# TA_kontroller.net
KiCad netlist of a schematic drawn in EAGLE
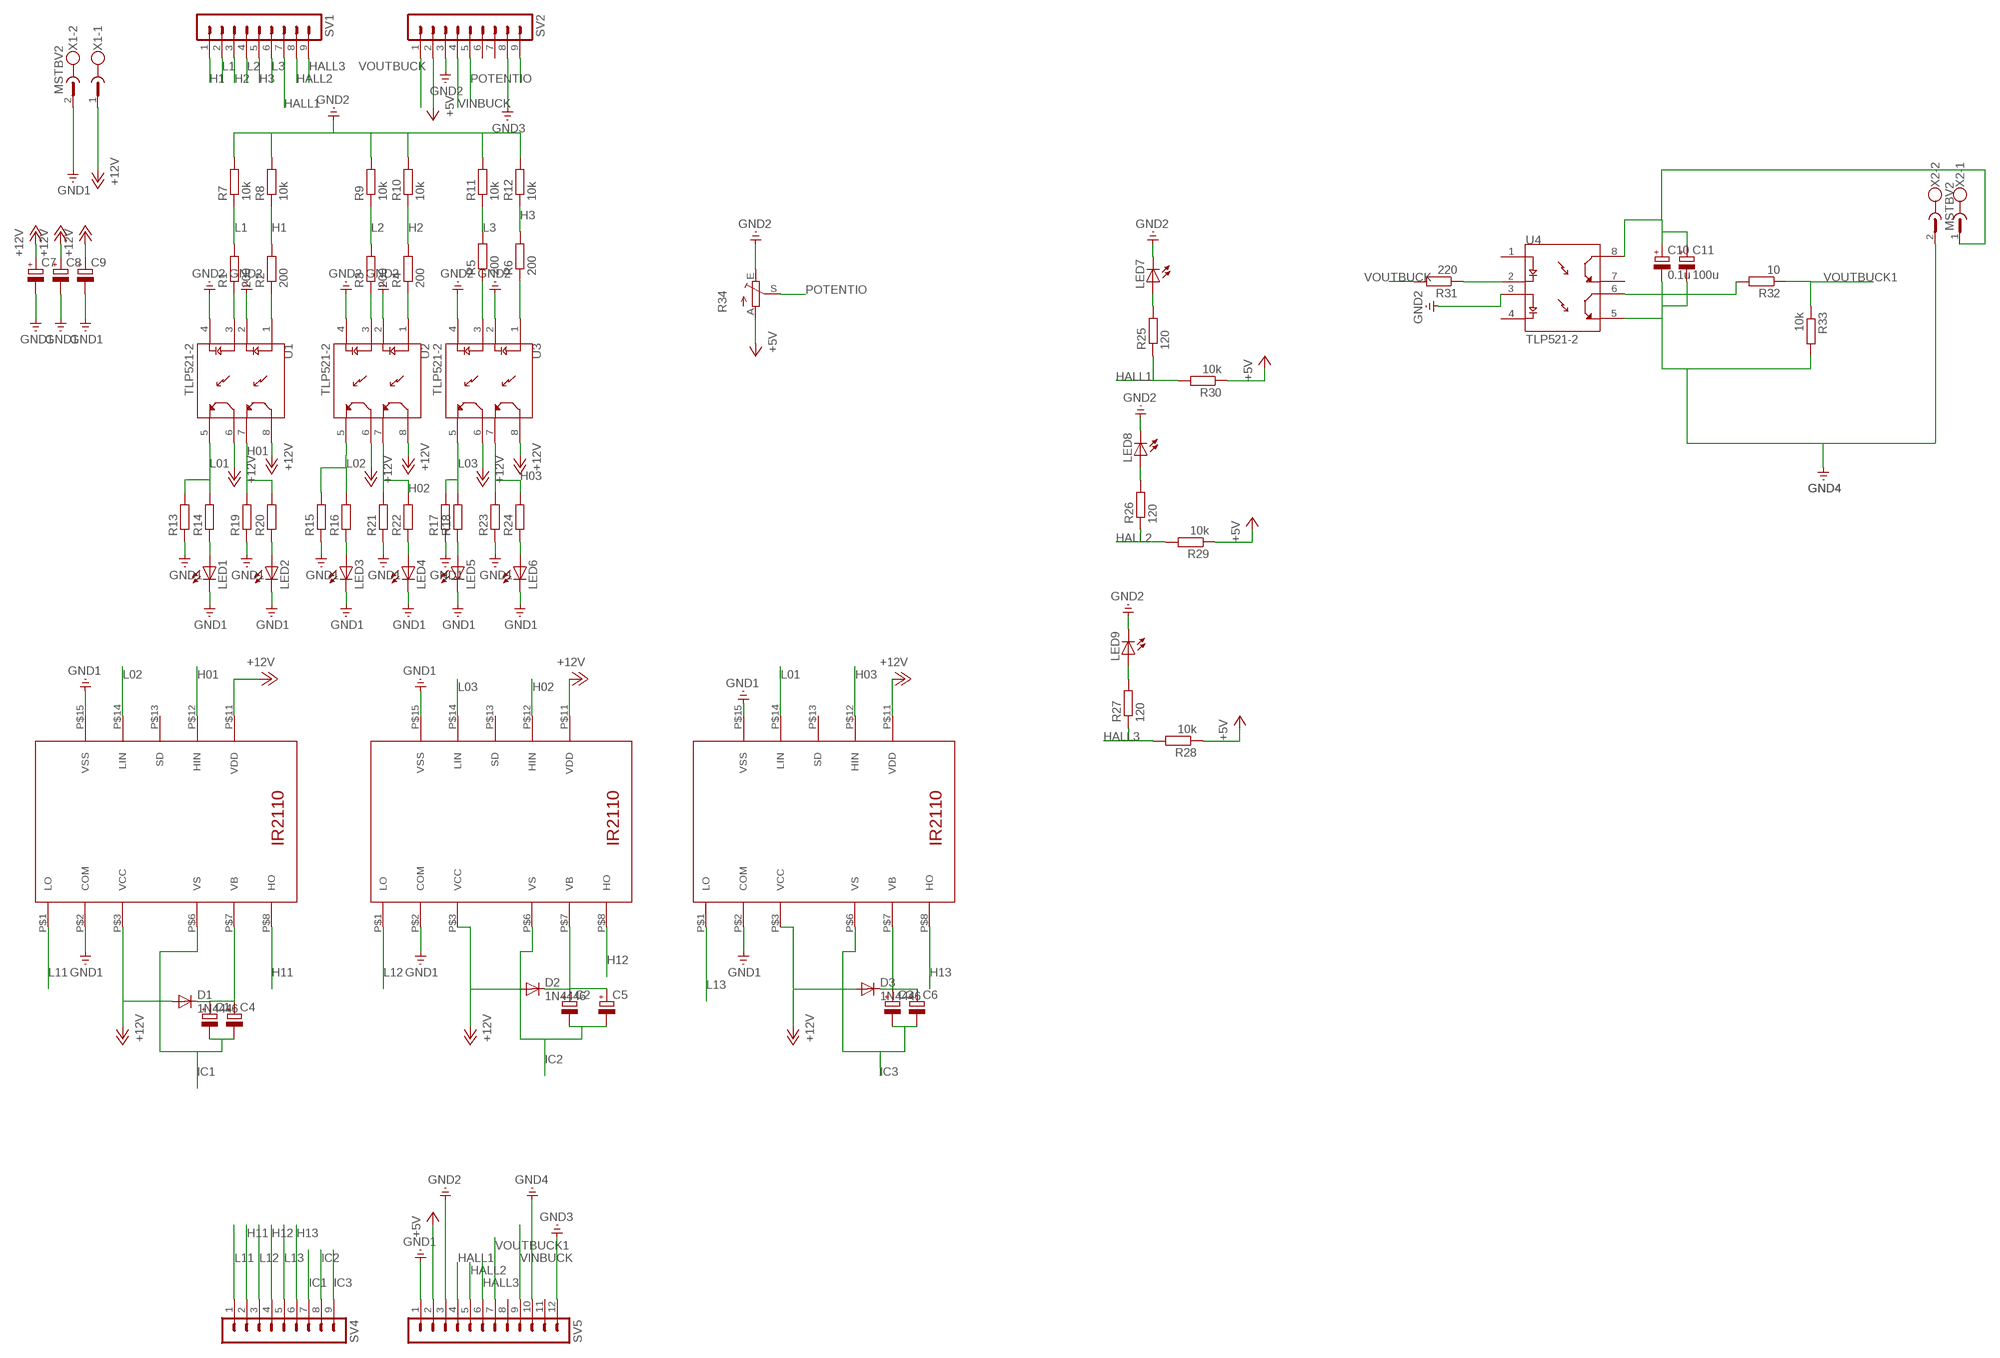
[diagram p0: schematic, sheet 1]

(export (version "E")
  (design (tool "Eeschema 10.0.6"))
  (components
    (comp (ref "C1")
      (value "CPOL-EUB45181C")
      (footprint "eagle-import:B45181C")
      (libsource (lib "eagle-import") (part "CPOL-EUB45181C"))
    )
    (comp (ref "C2")
      (value "CPOL-EUB45181C")
      (footprint "eagle-import:B45181C")
      (libsource (lib "eagle-import") (part "CPOL-EUB45181C"))
    )
    (comp (ref "C3")
      (value "CPOL-EUB45181C")
      (footprint "eagle-import:B45181C")
      (libsource (lib "eagle-import") (part "CPOL-EUB45181C"))
    )
    (comp (ref "C4")
      (value "CPOL-EUB45181C")
      (footprint "eagle-import:B45181C")
      (libsource (lib "eagle-import") (part "CPOL-EUB45181C"))
    )
    (comp (ref "C5")
      (value "CPOL-EUB45181C")
      (footprint "eagle-import:B45181C")
      (libsource (lib "eagle-import") (part "CPOL-EUB45181C"))
    )
    (comp (ref "C6")
      (value "CPOL-EUB45181C")
      (footprint "eagle-import:B45181C")
      (libsource (lib "eagle-import") (part "CPOL-EUB45181C"))
    )
    (comp (ref "C7")
      (value "CPOL-EUB45181C")
      (footprint "eagle-import:B45181C")
      (libsource (lib "eagle-import") (part "CPOL-EUB45181C"))
    )
    (comp (ref "C8")
      (value "CPOL-EUB45181C")
      (footprint "eagle-import:B45181C")
      (libsource (lib "eagle-import") (part "CPOL-EUB45181C"))
    )
    (comp (ref "C9")
      (value "CPOL-EUB45181C")
      (footprint "eagle-import:B45181C")
      (libsource (lib "eagle-import") (part "CPOL-EUB45181C"))
    )
    (comp (ref "C10")
      (value "0.1u")
      (footprint "eagle-import:B45181C")
      (libsource (lib "eagle-import") (part "CPOL-EUB45181C"))
    )
    (comp (ref "C11")
      (value "100u")
      (footprint "eagle-import:B45181C")
      (libsource (lib "eagle-import") (part "CPOL-EUB45181C"))
    )
    (comp (ref "D1")
      (value "1N4446")
      (footprint "eagle-import:DO35-10")
      (libsource (lib "eagle-import") (part "1N4446"))
    )
    (comp (ref "D2")
      (value "1N4446")
      (footprint "eagle-import:DO35-10")
      (libsource (lib "eagle-import") (part "1N4446"))
    )
    (comp (ref "D3")
      (value "1N4446")
      (footprint "eagle-import:DO35-10")
      (libsource (lib "eagle-import") (part "1N4446"))
    )
    (comp (ref "LED1")
      (value "LED3MM")
      (footprint "eagle-import:LED3MM")
      (libsource (lib "eagle-import") (part "LED3MM"))
    )
    (comp (ref "LED2")
      (value "LED3MM")
      (footprint "eagle-import:LED3MM")
      (libsource (lib "eagle-import") (part "LED3MM"))
    )
    (comp (ref "LED3")
      (value "LED3MM")
      (footprint "eagle-import:LED3MM")
      (libsource (lib "eagle-import") (part "LED3MM"))
    )
    (comp (ref "LED4")
      (value "LED3MM")
      (footprint "eagle-import:LED3MM")
      (libsource (lib "eagle-import") (part "LED3MM"))
    )
    (comp (ref "LED5")
      (value "LED3MM")
      (footprint "eagle-import:LED3MM")
      (libsource (lib "eagle-import") (part "LED3MM"))
    )
    (comp (ref "LED6")
      (value "LED3MM")
      (footprint "eagle-import:LED3MM")
      (libsource (lib "eagle-import") (part "LED3MM"))
    )
    (comp (ref "LED7")
      (value "LED3MM")
      (footprint "eagle-import:LED3MM")
      (libsource (lib "eagle-import") (part "LED3MM"))
    )
    (comp (ref "LED8")
      (value "LED3MM")
      (footprint "eagle-import:LED3MM")
      (libsource (lib "eagle-import") (part "LED3MM"))
    )
    (comp (ref "LED9")
      (value "LED3MM")
      (footprint "eagle-import:LED3MM")
      (libsource (lib "eagle-import") (part "LED3MM"))
    )
    (comp (ref "R1")
      (value "200")
      (footprint "eagle-import:0207_12")
      (libsource (lib "eagle-import") (part "R-EU_0207/12"))
    )
    (comp (ref "R2")
      (value "200")
      (footprint "eagle-import:0207_12")
      (libsource (lib "eagle-import") (part "R-EU_0207/12"))
    )
    (comp (ref "R3")
      (value "200")
      (footprint "eagle-import:0207_12")
      (libsource (lib "eagle-import") (part "R-EU_0207/12"))
    )
    (comp (ref "R4")
      (value "200")
      (footprint "eagle-import:0207_12")
      (libsource (lib "eagle-import") (part "R-EU_0207/12"))
    )
    (comp (ref "R5")
      (value "200")
      (footprint "eagle-import:0207_12")
      (libsource (lib "eagle-import") (part "R-EU_0207/12"))
    )
    (comp (ref "R6")
      (value "200")
      (footprint "eagle-import:0207_12")
      (libsource (lib "eagle-import") (part "R-EU_0207/12"))
    )
    (comp (ref "R7")
      (value "10k")
      (footprint "eagle-import:0207_12")
      (libsource (lib "eagle-import") (part "R-EU_0207/12"))
    )
    (comp (ref "R8")
      (value "10k")
      (footprint "eagle-import:0207_12")
      (libsource (lib "eagle-import") (part "R-EU_0207/12"))
    )
    (comp (ref "R9")
      (value "10k")
      (footprint "eagle-import:0207_12")
      (libsource (lib "eagle-import") (part "R-EU_0207/12"))
    )
    (comp (ref "R10")
      (value "10k")
      (footprint "eagle-import:0207_12")
      (libsource (lib "eagle-import") (part "R-EU_0207/12"))
    )
    (comp (ref "R11")
      (value "10k")
      (footprint "eagle-import:0207_12")
      (libsource (lib "eagle-import") (part "R-EU_0207/12"))
    )
    (comp (ref "R12")
      (value "10k")
      (footprint "eagle-import:0207_12")
      (libsource (lib "eagle-import") (part "R-EU_0207/12"))
    )
    (comp (ref "R13")
      (value "R-EU_0207/12")
      (footprint "eagle-import:0207_12")
      (libsource (lib "eagle-import") (part "R-EU_0207/12"))
    )
    (comp (ref "R14")
      (value "R-EU_0207/12")
      (footprint "eagle-import:0207_12")
      (libsource (lib "eagle-import") (part "R-EU_0207/12"))
    )
    (comp (ref "R15")
      (value "R-EU_0207/12")
      (footprint "eagle-import:0207_12")
      (libsource (lib "eagle-import") (part "R-EU_0207/12"))
    )
    (comp (ref "R16")
      (value "R-EU_0207/12")
      (footprint "eagle-import:0207_12")
      (libsource (lib "eagle-import") (part "R-EU_0207/12"))
    )
    (comp (ref "R17")
      (value "R-EU_0207/12")
      (footprint "eagle-import:0207_12")
      (libsource (lib "eagle-import") (part "R-EU_0207/12"))
    )
    (comp (ref "R18")
      (value "R-EU_0207/12")
      (footprint "eagle-import:0207_12")
      (libsource (lib "eagle-import") (part "R-EU_0207/12"))
    )
    (comp (ref "R19")
      (value "R-EU_0207/12")
      (footprint "eagle-import:0207_12")
      (libsource (lib "eagle-import") (part "R-EU_0207/12"))
    )
    (comp (ref "R20")
      (value "R-EU_0207/12")
      (footprint "eagle-import:0207_12")
      (libsource (lib "eagle-import") (part "R-EU_0207/12"))
    )
    (comp (ref "R21")
      (value "R-EU_0207/12")
      (footprint "eagle-import:0207_12")
      (libsource (lib "eagle-import") (part "R-EU_0207/12"))
    )
    (comp (ref "R22")
      (value "R-EU_0207/12")
      (footprint "eagle-import:0207_12")
      (libsource (lib "eagle-import") (part "R-EU_0207/12"))
    )
    (comp (ref "R23")
      (value "R-EU_0207/12")
      (footprint "eagle-import:0207_12")
      (libsource (lib "eagle-import") (part "R-EU_0207/12"))
    )
    (comp (ref "R24")
      (value "R-EU_0207/12")
      (footprint "eagle-import:0207_12")
      (libsource (lib "eagle-import") (part "R-EU_0207/12"))
    )
    (comp (ref "R25")
      (value "120")
      (footprint "eagle-import:0207_12")
      (libsource (lib "eagle-import") (part "R-EU_0207/12"))
    )
    (comp (ref "R26")
      (value "120")
      (footprint "eagle-import:0207_12")
      (libsource (lib "eagle-import") (part "R-EU_0207/12"))
    )
    (comp (ref "R27")
      (value "120")
      (footprint "eagle-import:0207_12")
      (libsource (lib "eagle-import") (part "R-EU_0207/12"))
    )
    (comp (ref "R28")
      (value "10k")
      (footprint "eagle-import:0207_12")
      (libsource (lib "eagle-import") (part "R-EU_0207/12"))
    )
    (comp (ref "R29")
      (value "10k")
      (footprint "eagle-import:0207_12")
      (libsource (lib "eagle-import") (part "R-EU_0207/12"))
    )
    (comp (ref "R30")
      (value "10k")
      (footprint "eagle-import:0207_12")
      (libsource (lib "eagle-import") (part "R-EU_0207/12"))
    )
    (comp (ref "R31")
      (value "220")
      (footprint "eagle-import:0207_12")
      (libsource (lib "eagle-import") (part "R-EU_0207/12"))
    )
    (comp (ref "R32")
      (value "10")
      (footprint "eagle-import:0207_12")
      (libsource (lib "eagle-import") (part "R-EU_0207/12"))
    )
    (comp (ref "R33")
      (value "10k")
      (footprint "eagle-import:0207_12")
      (libsource (lib "eagle-import") (part "R-EU_0207/12"))
    )
    (comp (ref "R34")
      (value "TRIM_EU-B25V")
      (footprint "eagle-import:B25V")
      (libsource (lib "eagle-import") (part "TRIM_EU-B25V"))
    )
    (comp (ref "SV1")
      (value "MA09-1")
      (footprint "eagle-import:MA09-1")
      (libsource (lib "eagle-import") (part "MA09-1"))
    )
    (comp (ref "SV2")
      (value "MA09-1")
      (footprint "eagle-import:MA09-1")
      (libsource (lib "eagle-import") (part "MA09-1"))
    )
    (comp (ref "SV4")
      (value "MA09-1")
      (footprint "eagle-import:MA09-1")
      (libsource (lib "eagle-import") (part "MA09-1"))
    )
    (comp (ref "SV5")
      (value "MA12-1")
      (footprint "eagle-import:MA12-1")
      (libsource (lib "eagle-import") (part "MA12-1"))
    )
    (comp (ref "U$1")
      (value "IR2110")
      (footprint "eagle-import:DIL16")
      (libsource (lib "eagle-import") (part "IR2110"))
    )
    (comp (ref "U$2")
      (value "IR2110")
      (footprint "eagle-import:DIL16")
      (libsource (lib "eagle-import") (part "IR2110"))
    )
    (comp (ref "U$3")
      (value "IR2110")
      (footprint "eagle-import:DIL16")
      (libsource (lib "eagle-import") (part "IR2110"))
    )
    (comp (ref "U1")
      (value "TLP521-2")
      (footprint "eagle-import:DIP762W50P254L1018H451Q8")
      (fields (field (name "MF") "Isocom"))
      (libsource (lib "eagle-import") (part "TLP521-2"))
    )
    (comp (ref "U2")
      (value "TLP521-2")
      (footprint "eagle-import:DIP762W50P254L1018H451Q8")
      (fields (field (name "MF") "Isocom"))
      (libsource (lib "eagle-import") (part "TLP521-2"))
    )
    (comp (ref "U3")
      (value "TLP521-2")
      (footprint "eagle-import:DIP762W50P254L1018H451Q8")
      (fields (field (name "MF") "Isocom"))
      (libsource (lib "eagle-import") (part "TLP521-2"))
    )
    (comp (ref "U4")
      (value "TLP521-2")
      (footprint "eagle-import:DIP762W50P254L1018H451Q8")
      (fields (field (name "MF") "Isocom"))
      (libsource (lib "eagle-import") (part "TLP521-2"))
    )
    (comp (ref "X1")
      (value "MSTBV2")
      (footprint "eagle-import:MSTBV2")
      (fields (field (name "MPN") "MSTBV 2,5/2-GF-5.08"))
      (libsource (lib "eagle-import") (part "MSTBV2"))
    )
    (comp (ref "X2")
      (value "MSTBV2")
      (footprint "eagle-import:MSTBV2")
      (fields (field (name "MPN") "MSTBV 2,5/2-GF-5.08"))
      (libsource (lib "eagle-import") (part "MSTBV2"))
    )
  )
  (nets
    (net (code "1") (name "+5V") (class "Default")
      (node (ref "R28") (pin "1") (pinfunction "1_1") (pintype "passive"))
      (node (ref "R29") (pin "1") (pinfunction "1_1") (pintype "passive"))
      (node (ref "R30") (pin "1") (pinfunction "1_1") (pintype "passive"))
      (node (ref "R34") (pin "A") (pinfunction "A_A") (pintype "passive"))
      (node (ref "SV2") (pin "2") (pinfunction "2_2") (pintype "passive"))
      (node (ref "SV5") (pin "2") (pinfunction "2_2") (pintype "passive"))
    )
    (net (code "2") (name "+12V") (class "Default")
      (node (ref "C7") (pin "+") (pinfunction "+_+") (pintype "passive"))
      (node (ref "C8") (pin "+") (pinfunction "+_+") (pintype "passive"))
      (node (ref "C9") (pin "+") (pinfunction "+_+") (pintype "passive"))
      (node (ref "D1") (pin "A") (pinfunction "A_A") (pintype "passive"))
      (node (ref "D2") (pin "A") (pinfunction "A_A") (pintype "passive"))
      (node (ref "D3") (pin "A") (pinfunction "A_A") (pintype "passive"))
      (node (ref "U$1") (pin "P$11") (pinfunction "VDD_P$11") (pintype "bidirectional"))
      (node (ref "U$1") (pin "P$3") (pinfunction "VCC_P$3") (pintype "bidirectional"))
      (node (ref "U$2") (pin "P$11") (pinfunction "VDD_P$11") (pintype "bidirectional"))
      (node (ref "U$2") (pin "P$3") (pinfunction "VCC_P$3") (pintype "bidirectional"))
      (node (ref "U$3") (pin "P$11") (pinfunction "VDD_P$11") (pintype "bidirectional"))
      (node (ref "U$3") (pin "P$3") (pinfunction "VCC_P$3") (pintype "bidirectional"))
      (node (ref "U1") (pin "6") (pinfunction "6_6") (pintype "passive"))
      (node (ref "U1") (pin "8") (pinfunction "8_8") (pintype "passive"))
      (node (ref "U2") (pin "6") (pinfunction "6_6") (pintype "passive"))
      (node (ref "U2") (pin "8") (pinfunction "8_8") (pintype "passive"))
      (node (ref "U3") (pin "6") (pinfunction "6_6") (pintype "passive"))
      (node (ref "U3") (pin "8") (pinfunction "8_8") (pintype "passive"))
      (node (ref "X1") (pin "1") (pinfunction "1_1") (pintype "passive"))
    )
    (net (code "3") (name "/H01") (class "Default")
      (node (ref "R19") (pin "2") (pinfunction "2_2") (pintype "passive"))
      (node (ref "R20") (pin "2") (pinfunction "2_2") (pintype "passive"))
      (node (ref "U$1") (pin "P$12") (pinfunction "HIN_P$12") (pintype "bidirectional"))
      (node (ref "U1") (pin "7") (pinfunction "7_7") (pintype "passive"))
    )
    (net (code "4") (name "/H1") (class "Default")
      (node (ref "R2") (pin "2") (pinfunction "2_2") (pintype "passive"))
      (node (ref "R8") (pin "1") (pinfunction "1_1") (pintype "passive"))
      (node (ref "SV1") (pin "1") (pinfunction "1_1") (pintype "passive"))
    )
    (net (code "5") (name "/H02") (class "Default")
      (node (ref "R21") (pin "2") (pinfunction "2_2") (pintype "passive"))
      (node (ref "R22") (pin "2") (pinfunction "2_2") (pintype "passive"))
      (node (ref "U$2") (pin "P$12") (pinfunction "HIN_P$12") (pintype "bidirectional"))
      (node (ref "U2") (pin "7") (pinfunction "7_7") (pintype "passive"))
    )
    (net (code "6") (name "/H2") (class "Default")
      (node (ref "R10") (pin "1") (pinfunction "1_1") (pintype "passive"))
      (node (ref "R4") (pin "2") (pinfunction "2_2") (pintype "passive"))
      (node (ref "SV1") (pin "3") (pinfunction "3_3") (pintype "passive"))
    )
    (net (code "7") (name "/H3") (class "Default")
      (node (ref "R12") (pin "1") (pinfunction "1_1") (pintype "passive"))
      (node (ref "R6") (pin "2") (pinfunction "2_2") (pintype "passive"))
      (node (ref "SV1") (pin "5") (pinfunction "5_5") (pintype "passive"))
    )
    (net (code "8") (name "/H03") (class "Default")
      (node (ref "R23") (pin "2") (pinfunction "2_2") (pintype "passive"))
      (node (ref "R24") (pin "2") (pinfunction "2_2") (pintype "passive"))
      (node (ref "U$3") (pin "P$12") (pinfunction "HIN_P$12") (pintype "bidirectional"))
      (node (ref "U3") (pin "7") (pinfunction "7_7") (pintype "passive"))
    )
    (net (code "9") (name "/H11") (class "Default")
      (node (ref "SV4") (pin "2") (pinfunction "2_2") (pintype "passive"))
      (node (ref "U$1") (pin "P$8") (pinfunction "HO_P$8") (pintype "bidirectional"))
    )
    (net (code "10") (name "/H12") (class "Default")
      (node (ref "SV4") (pin "4") (pinfunction "4_4") (pintype "passive"))
      (node (ref "U$2") (pin "P$8") (pinfunction "HO_P$8") (pintype "bidirectional"))
    )
    (net (code "11") (name "/H13") (class "Default")
      (node (ref "SV4") (pin "6") (pinfunction "6_6") (pintype "passive"))
      (node (ref "U$3") (pin "P$8") (pinfunction "HO_P$8") (pintype "bidirectional"))
    )
    (net (code "12") (name "/HALL1") (class "Default")
      (node (ref "R25") (pin "1") (pinfunction "1_1") (pintype "passive"))
      (node (ref "R30") (pin "2") (pinfunction "2_2") (pintype "passive"))
      (node (ref "SV1") (pin "7") (pinfunction "7_7") (pintype "passive"))
      (node (ref "SV5") (pin "4") (pinfunction "4_4") (pintype "passive"))
    )
    (net (code "13") (name "/HALL2") (class "Default")
      (node (ref "R26") (pin "1") (pinfunction "1_1") (pintype "passive"))
      (node (ref "R29") (pin "2") (pinfunction "2_2") (pintype "passive"))
      (node (ref "SV1") (pin "8") (pinfunction "8_8") (pintype "passive"))
      (node (ref "SV5") (pin "5") (pinfunction "5_5") (pintype "passive"))
    )
    (net (code "14") (name "/HALL3") (class "Default")
      (node (ref "R27") (pin "1") (pinfunction "1_1") (pintype "passive"))
      (node (ref "R28") (pin "2") (pinfunction "2_2") (pintype "passive"))
      (node (ref "SV1") (pin "9") (pinfunction "9_9") (pintype "passive"))
      (node (ref "SV5") (pin "6") (pinfunction "6_6") (pintype "passive"))
    )
    (net (code "15") (name "/IC1") (class "Default")
      (node (ref "C1") (pin "-") (pinfunction "-_-") (pintype "passive"))
      (node (ref "C4") (pin "-") (pinfunction "-_-") (pintype "passive"))
      (node (ref "SV4") (pin "7") (pinfunction "7_7") (pintype "passive"))
      (node (ref "U$1") (pin "P$6") (pinfunction "VS_P$6") (pintype "bidirectional"))
    )
    (net (code "16") (name "/IC2") (class "Default")
      (node (ref "C2") (pin "-") (pinfunction "-_-") (pintype "passive"))
      (node (ref "C5") (pin "-") (pinfunction "-_-") (pintype "passive"))
      (node (ref "SV4") (pin "8") (pinfunction "8_8") (pintype "passive"))
      (node (ref "U$2") (pin "P$6") (pinfunction "VS_P$6") (pintype "bidirectional"))
    )
    (net (code "17") (name "/IC3") (class "Default")
      (node (ref "C3") (pin "-") (pinfunction "-_-") (pintype "passive"))
      (node (ref "C6") (pin "-") (pinfunction "-_-") (pintype "passive"))
      (node (ref "SV4") (pin "9") (pinfunction "9_9") (pintype "passive"))
      (node (ref "U$3") (pin "P$6") (pinfunction "VS_P$6") (pintype "bidirectional"))
    )
    (net (code "18") (name "/L1") (class "Default")
      (node (ref "R1") (pin "2") (pinfunction "2_2") (pintype "passive"))
      (node (ref "R7") (pin "1") (pinfunction "1_1") (pintype "passive"))
      (node (ref "SV1") (pin "2") (pinfunction "2_2") (pintype "passive"))
    )
    (net (code "19") (name "/L01") (class "Default")
      (node (ref "R13") (pin "2") (pinfunction "2_2") (pintype "passive"))
      (node (ref "R14") (pin "2") (pinfunction "2_2") (pintype "passive"))
      (node (ref "U$3") (pin "P$14") (pinfunction "LIN_P$14") (pintype "bidirectional"))
      (node (ref "U1") (pin "5") (pinfunction "5_5") (pintype "passive"))
    )
    (net (code "20") (name "/L2") (class "Default")
      (node (ref "R3") (pin "2") (pinfunction "2_2") (pintype "passive"))
      (node (ref "R9") (pin "1") (pinfunction "1_1") (pintype "passive"))
      (node (ref "SV1") (pin "4") (pinfunction "4_4") (pintype "passive"))
    )
    (net (code "21") (name "/L02") (class "Default")
      (node (ref "R15") (pin "2") (pinfunction "2_2") (pintype "passive"))
      (node (ref "R16") (pin "2") (pinfunction "2_2") (pintype "passive"))
      (node (ref "U$1") (pin "P$14") (pinfunction "LIN_P$14") (pintype "bidirectional"))
      (node (ref "U2") (pin "5") (pinfunction "5_5") (pintype "passive"))
    )
    (net (code "22") (name "/L3") (class "Default")
      (node (ref "R11") (pin "1") (pinfunction "1_1") (pintype "passive"))
      (node (ref "R5") (pin "2") (pinfunction "2_2") (pintype "passive"))
      (node (ref "SV1") (pin "6") (pinfunction "6_6") (pintype "passive"))
    )
    (net (code "23") (name "/L03") (class "Default")
      (node (ref "R17") (pin "2") (pinfunction "2_2") (pintype "passive"))
      (node (ref "R18") (pin "2") (pinfunction "2_2") (pintype "passive"))
      (node (ref "U$2") (pin "P$14") (pinfunction "LIN_P$14") (pintype "bidirectional"))
      (node (ref "U3") (pin "5") (pinfunction "5_5") (pintype "passive"))
    )
    (net (code "24") (name "/L11") (class "Default")
      (node (ref "SV4") (pin "1") (pinfunction "1_1") (pintype "passive"))
      (node (ref "U$1") (pin "P$1") (pinfunction "LO_P$1") (pintype "bidirectional"))
    )
    (net (code "25") (name "/L12") (class "Default")
      (node (ref "SV4") (pin "3") (pinfunction "3_3") (pintype "passive"))
      (node (ref "U$2") (pin "P$1") (pinfunction "LO_P$1") (pintype "bidirectional"))
    )
    (net (code "26") (name "/L13") (class "Default")
      (node (ref "SV4") (pin "5") (pinfunction "5_5") (pintype "passive"))
      (node (ref "U$3") (pin "P$1") (pinfunction "LO_P$1") (pintype "bidirectional"))
    )
    (net (code "27") (name "/POTENTIO") (class "Default")
      (node (ref "R34") (pin "S") (pinfunction "S_S") (pintype "passive"))
      (node (ref "SV2") (pin "5") (pinfunction "5_5") (pintype "passive"))
    )
    (net (code "28") (name "/V2") (class "Default")
      (node (ref "C10") (pin "+") (pinfunction "+_+") (pintype "passive"))
      (node (ref "C11") (pin "+") (pinfunction "+_+") (pintype "passive"))
      (node (ref "SV2") (pin "9") (pinfunction "9_9") (pintype "passive"))
      (node (ref "U4") (pin "8") (pinfunction "8_8") (pintype "passive"))
      (node (ref "X2") (pin "1") (pinfunction "1_1") (pintype "passive"))
    )
    (net (code "29") (name "/VINBUCK") (class "Default")
      (node (ref "SV2") (pin "4") (pinfunction "4_4") (pintype "passive"))
      (node (ref "SV5") (pin "9") (pinfunction "9_9") (pintype "passive"))
    )
    (net (code "30") (name "/VOUTBUCK") (class "Default")
      (node (ref "R31") (pin "2") (pinfunction "2_2") (pintype "passive"))
      (node (ref "SV2") (pin "1") (pinfunction "1_1") (pintype "passive"))
    )
    (net (code "31") (name "/VOUTBUCK1") (class "Default")
      (node (ref "R32") (pin "1") (pinfunction "1_1") (pintype "passive"))
      (node (ref "R33") (pin "1") (pinfunction "1_1") (pintype "passive"))
      (node (ref "SV5") (pin "7") (pinfunction "7_7") (pintype "passive"))
    )
    (net (code "32") (name "GND1") (class "Default")
      (node (ref "C7") (pin "-") (pinfunction "-_-") (pintype "passive"))
      (node (ref "C8") (pin "-") (pinfunction "-_-") (pintype "passive"))
      (node (ref "C9") (pin "-") (pinfunction "-_-") (pintype "passive"))
      (node (ref "LED1") (pin "K") (pinfunction "C_K") (pintype "passive"))
      (node (ref "LED2") (pin "K") (pinfunction "C_K") (pintype "passive"))
      (node (ref "LED3") (pin "K") (pinfunction "C_K") (pintype "passive"))
      (node (ref "LED4") (pin "K") (pinfunction "C_K") (pintype "passive"))
      (node (ref "LED5") (pin "K") (pinfunction "C_K") (pintype "passive"))
      (node (ref "LED6") (pin "K") (pinfunction "C_K") (pintype "passive"))
      (node (ref "R13") (pin "1") (pinfunction "1_1") (pintype "passive"))
      (node (ref "R15") (pin "1") (pinfunction "1_1") (pintype "passive"))
      (node (ref "R17") (pin "1") (pinfunction "1_1") (pintype "passive"))
      (node (ref "R19") (pin "1") (pinfunction "1_1") (pintype "passive"))
      (node (ref "R21") (pin "1") (pinfunction "1_1") (pintype "passive"))
      (node (ref "R23") (pin "1") (pinfunction "1_1") (pintype "passive"))
      (node (ref "SV5") (pin "1") (pinfunction "1_1") (pintype "passive"))
      (node (ref "U$1") (pin "P$15") (pinfunction "VSS_P$15") (pintype "bidirectional"))
      (node (ref "U$1") (pin "P$2") (pinfunction "COM_P$2") (pintype "bidirectional"))
      (node (ref "U$2") (pin "P$15") (pinfunction "VSS_P$15") (pintype "bidirectional"))
      (node (ref "U$2") (pin "P$2") (pinfunction "COM_P$2") (pintype "bidirectional"))
      (node (ref "U$3") (pin "P$15") (pinfunction "VSS_P$15") (pintype "bidirectional"))
      (node (ref "U$3") (pin "P$2") (pinfunction "COM_P$2") (pintype "bidirectional"))
      (node (ref "X1") (pin "2") (pinfunction "1_2") (pintype "passive"))
    )
    (net (code "33") (name "GND2") (class "Default")
      (node (ref "LED7") (pin "K") (pinfunction "C_K") (pintype "passive"))
      (node (ref "LED8") (pin "K") (pinfunction "C_K") (pintype "passive"))
      (node (ref "LED9") (pin "K") (pinfunction "C_K") (pintype "passive"))
      (node (ref "R10") (pin "2") (pinfunction "2_2") (pintype "passive"))
      (node (ref "R11") (pin "2") (pinfunction "2_2") (pintype "passive"))
      (node (ref "R12") (pin "2") (pinfunction "2_2") (pintype "passive"))
      (node (ref "R34") (pin "E") (pinfunction "E_E") (pintype "passive"))
      (node (ref "R7") (pin "2") (pinfunction "2_2") (pintype "passive"))
      (node (ref "R8") (pin "2") (pinfunction "2_2") (pintype "passive"))
      (node (ref "R9") (pin "2") (pinfunction "2_2") (pintype "passive"))
      (node (ref "SV2") (pin "3") (pinfunction "3_3") (pintype "passive"))
      (node (ref "SV5") (pin "3") (pinfunction "3_3") (pintype "passive"))
      (node (ref "U1") (pin "2") (pinfunction "2_2") (pintype "passive"))
      (node (ref "U1") (pin "4") (pinfunction "4_4") (pintype "passive"))
      (node (ref "U2") (pin "2") (pinfunction "2_2") (pintype "passive"))
      (node (ref "U2") (pin "4") (pinfunction "4_4") (pintype "passive"))
      (node (ref "U3") (pin "2") (pinfunction "2_2") (pintype "passive"))
      (node (ref "U3") (pin "4") (pinfunction "4_4") (pintype "passive"))
      (node (ref "U4") (pin "3") (pinfunction "3_3") (pintype "passive"))
    )
    (net (code "34") (name "GND3") (class "Default")
      (node (ref "SV2") (pin "8") (pinfunction "8_8") (pintype "passive"))
      (node (ref "SV5") (pin "12") (pinfunction "12_12") (pintype "passive"))
    )
    (net (code "35") (name "GND4") (class "Default")
      (node (ref "C10") (pin "-") (pinfunction "-_-") (pintype "passive"))
      (node (ref "C11") (pin "-") (pinfunction "-_-") (pintype "passive"))
      (node (ref "R33") (pin "2") (pinfunction "2_2") (pintype "passive"))
      (node (ref "SV5") (pin "10") (pinfunction "10_10") (pintype "passive"))
      (node (ref "U4") (pin "5") (pinfunction "5_5") (pintype "passive"))
      (node (ref "X2") (pin "2") (pinfunction "1_2") (pintype "passive"))
    )
    (net (code "36") (name "Net-(LED1-PadA)") (class "Default")
      (node (ref "LED1") (pin "A") (pinfunction "A_A") (pintype "passive"))
      (node (ref "R14") (pin "1") (pinfunction "1_1") (pintype "passive"))
    )
    (net (code "37") (name "Net-(LED2-PadA)") (class "Default")
      (node (ref "LED2") (pin "A") (pinfunction "A_A") (pintype "passive"))
      (node (ref "R20") (pin "1") (pinfunction "1_1") (pintype "passive"))
    )
    (net (code "38") (name "Net-(LED3-PadA)") (class "Default")
      (node (ref "LED3") (pin "A") (pinfunction "A_A") (pintype "passive"))
      (node (ref "R16") (pin "1") (pinfunction "1_1") (pintype "passive"))
    )
    (net (code "39") (name "Net-(LED4-PadA)") (class "Default")
      (node (ref "LED4") (pin "A") (pinfunction "A_A") (pintype "passive"))
      (node (ref "R22") (pin "1") (pinfunction "1_1") (pintype "passive"))
    )
    (net (code "40") (name "Net-(LED5-PadA)") (class "Default")
      (node (ref "LED5") (pin "A") (pinfunction "A_A") (pintype "passive"))
      (node (ref "R18") (pin "1") (pinfunction "1_1") (pintype "passive"))
    )
    (net (code "41") (name "Net-(LED6-PadA)") (class "Default")
      (node (ref "LED6") (pin "A") (pinfunction "A_A") (pintype "passive"))
      (node (ref "R24") (pin "1") (pinfunction "1_1") (pintype "passive"))
    )
    (net (code "42") (name "Net-(LED7-PadA)") (class "Default")
      (node (ref "LED7") (pin "A") (pinfunction "A_A") (pintype "passive"))
      (node (ref "R25") (pin "2") (pinfunction "2_2") (pintype "passive"))
    )
    (net (code "43") (name "Net-(LED8-PadA)") (class "Default")
      (node (ref "LED8") (pin "A") (pinfunction "A_A") (pintype "passive"))
      (node (ref "R26") (pin "2") (pinfunction "2_2") (pintype "passive"))
    )
    (net (code "44") (name "Net-(LED9-PadA)") (class "Default")
      (node (ref "LED9") (pin "A") (pinfunction "A_A") (pintype "passive"))
      (node (ref "R27") (pin "2") (pinfunction "2_2") (pintype "passive"))
    )
    (net (code "45") (name "Net-(R1-Pad1)") (class "Default")
      (node (ref "R1") (pin "1") (pinfunction "1_1") (pintype "passive"))
      (node (ref "U1") (pin "3") (pinfunction "3_3") (pintype "passive"))
    )
    (net (code "46") (name "Net-(R2-Pad1)") (class "Default")
      (node (ref "R2") (pin "1") (pinfunction "1_1") (pintype "passive"))
      (node (ref "U1") (pin "1") (pinfunction "1_1") (pintype "passive"))
    )
    (net (code "47") (name "Net-(R3-Pad1)") (class "Default")
      (node (ref "R3") (pin "1") (pinfunction "1_1") (pintype "passive"))
      (node (ref "U2") (pin "3") (pinfunction "3_3") (pintype "passive"))
    )
    (net (code "48") (name "Net-(R4-Pad1)") (class "Default")
      (node (ref "R4") (pin "1") (pinfunction "1_1") (pintype "passive"))
      (node (ref "U2") (pin "1") (pinfunction "1_1") (pintype "passive"))
    )
    (net (code "49") (name "Net-(R5-Pad1)") (class "Default")
      (node (ref "R5") (pin "1") (pinfunction "1_1") (pintype "passive"))
      (node (ref "U3") (pin "3") (pinfunction "3_3") (pintype "passive"))
    )
    (net (code "50") (name "Net-(R6-Pad1)") (class "Default")
      (node (ref "R6") (pin "1") (pinfunction "1_1") (pintype "passive"))
      (node (ref "U3") (pin "1") (pinfunction "1_1") (pintype "passive"))
    )
    (net (code "51") (name "Net-(R31-Pad1)") (class "Default")
      (node (ref "R31") (pin "1") (pinfunction "1_1") (pintype "passive"))
      (node (ref "U4") (pin "2") (pinfunction "2_2") (pintype "passive"))
    )
    (net (code "52") (name "Net-(R32-Pad2)") (class "Default")
      (node (ref "R32") (pin "2") (pinfunction "2_2") (pintype "passive"))
      (node (ref "U4") (pin "6") (pinfunction "6_6") (pintype "passive"))
    )
    (net (code "53") (name "Net-(U$1-VB)") (class "Default")
      (node (ref "C1") (pin "+") (pinfunction "+_+") (pintype "passive"))
      (node (ref "C4") (pin "+") (pinfunction "+_+") (pintype "passive"))
      (node (ref "D1") (pin "C") (pinfunction "C_C") (pintype "passive"))
      (node (ref "U$1") (pin "P$7") (pinfunction "VB_P$7") (pintype "bidirectional"))
    )
    (net (code "54") (name "Net-(U$2-VB)") (class "Default")
      (node (ref "C2") (pin "+") (pinfunction "+_+") (pintype "passive"))
      (node (ref "C5") (pin "+") (pinfunction "+_+") (pintype "passive"))
      (node (ref "D2") (pin "C") (pinfunction "C_C") (pintype "passive"))
      (node (ref "U$2") (pin "P$7") (pinfunction "VB_P$7") (pintype "bidirectional"))
    )
    (net (code "55") (name "Net-(U$3-VB)") (class "Default")
      (node (ref "C3") (pin "+") (pinfunction "+_+") (pintype "passive"))
      (node (ref "C6") (pin "+") (pinfunction "+_+") (pintype "passive"))
      (node (ref "D3") (pin "C") (pinfunction "C_C") (pintype "passive"))
      (node (ref "U$3") (pin "P$7") (pinfunction "VB_P$7") (pintype "bidirectional"))
    )
    (net (code "56") (name "unconnected-(SV2-Pad6)") (class "Default")
      (node (ref "SV2") (pin "6") (pinfunction "6_6") (pintype "passive"))
    )
    (net (code "57") (name "unconnected-(SV2-Pad7)") (class "Default")
      (node (ref "SV2") (pin "7") (pinfunction "7_7") (pintype "passive"))
    )
    (net (code "58") (name "unconnected-(SV5-Pad8)") (class "Default")
      (node (ref "SV5") (pin "8") (pinfunction "8_8") (pintype "passive"))
    )
    (net (code "59") (name "unconnected-(SV5-Pad11)") (class "Default")
      (node (ref "SV5") (pin "11") (pinfunction "11_11") (pintype "passive"))
    )
    (net (code "60") (name "unconnected-(U$1-SD-PadP$13)") (class "Default")
      (node (ref "U$1") (pin "P$13") (pinfunction "SD_P$13") (pintype "bidirectional"))
    )
    (net (code "61") (name "unconnected-(U$2-SD-PadP$13)") (class "Default")
      (node (ref "U$2") (pin "P$13") (pinfunction "SD_P$13") (pintype "bidirectional"))
    )
    (net (code "62") (name "unconnected-(U$3-SD-PadP$13)") (class "Default")
      (node (ref "U$3") (pin "P$13") (pinfunction "SD_P$13") (pintype "bidirectional"))
    )
    (net (code "63") (name "unconnected-(U4-Pad1)") (class "Default")
      (node (ref "U4") (pin "1") (pinfunction "1_1") (pintype "passive"))
    )
    (net (code "64") (name "unconnected-(U4-Pad4)") (class "Default")
      (node (ref "U4") (pin "4") (pinfunction "4_4") (pintype "passive"))
    )
    (net (code "65") (name "unconnected-(U4-Pad7)") (class "Default")
      (node (ref "U4") (pin "7") (pinfunction "7_7") (pintype "passive"))
    )
  )
)
